# VER2.net
KiCad netlist of a schematic drawn in EAGLE
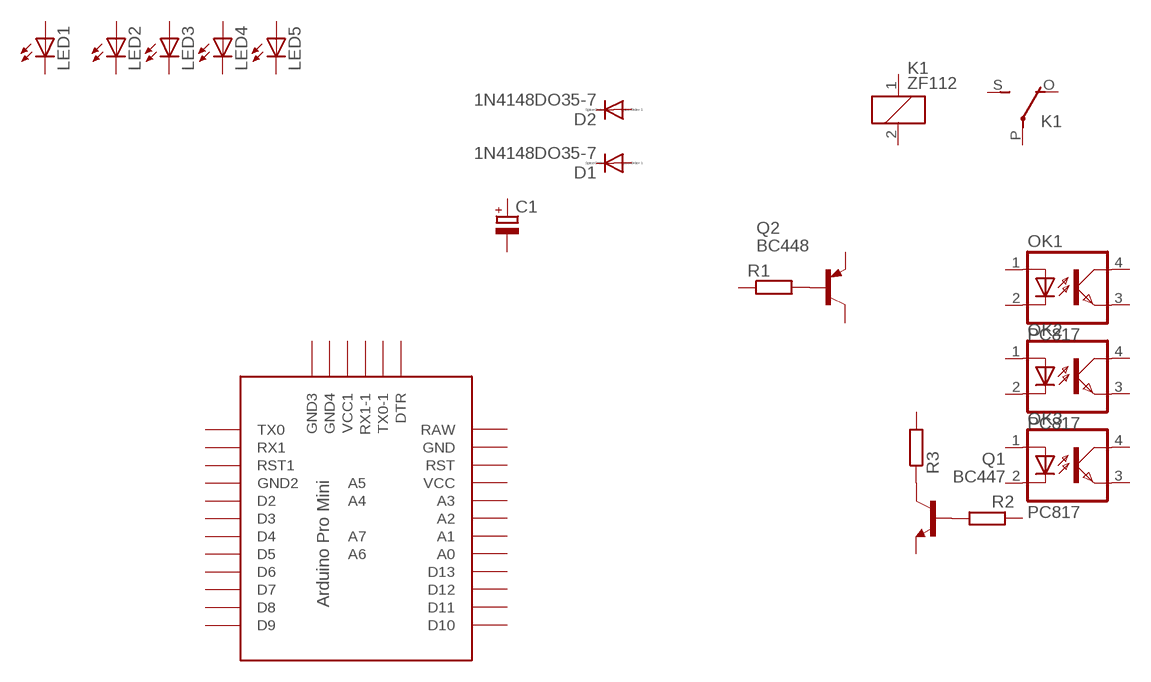
[diagram p0: schematic, sheet 1]

(export (version "E")
  (design (tool "Eeschema 10.0.6"))
  (components
    (comp (ref "C1")
      (value "CPOL-EUE5-6")
      (footprint "eagle-import:E5-6")
      (libsource (lib "eagle-import") (part "CPOL-EUE5-6"))
    )
    (comp (ref "D1")
      (value "1N4148DO35-7")
      (footprint "eagle-import:DO35-7")
      (libsource (lib "eagle-import") (part "1N4148DO35-7"))
    )
    (comp (ref "D2")
      (value "1N4148DO35-7")
      (footprint "eagle-import:DO35-7")
      (libsource (lib "eagle-import") (part "1N4148DO35-7"))
    )
    (comp (ref "K1")
      (value "ZF112")
      (footprint "eagle-import:ZF112")
      (libsource (lib "eagle-import") (part "ZF112"))
    )
    (comp (ref "LED1")
      (value "LED5MM")
      (footprint "eagle-import:LED5MM")
      (libsource (lib "eagle-import") (part "LED5MM"))
    )
    (comp (ref "LED2")
      (value "LED5MM")
      (footprint "eagle-import:LED5MM")
      (libsource (lib "eagle-import") (part "LED5MM"))
    )
    (comp (ref "LED3")
      (value "LED5MM")
      (footprint "eagle-import:LED5MM")
      (libsource (lib "eagle-import") (part "LED5MM"))
    )
    (comp (ref "LED4")
      (value "LED5MM")
      (footprint "eagle-import:LED5MM")
      (libsource (lib "eagle-import") (part "LED5MM"))
    )
    (comp (ref "LED5")
      (value "LED5MM")
      (footprint "eagle-import:LED5MM")
      (libsource (lib "eagle-import") (part "LED5MM"))
    )
    (comp (ref "OK1")
      (value "PC817")
      (footprint "eagle-import:DIL04")
      (fields (field (name "MPN") "PC817X4J000F"))
      (libsource (lib "eagle-import") (part "PC817"))
    )
    (comp (ref "OK2")
      (value "PC817")
      (footprint "eagle-import:DIL04")
      (fields (field (name "MPN") "PC817X4J000F"))
      (libsource (lib "eagle-import") (part "PC817"))
    )
    (comp (ref "OK3")
      (value "PC817")
      (footprint "eagle-import:DIL04")
      (fields (field (name "MPN") "PC817X4J000F"))
      (libsource (lib "eagle-import") (part "PC817"))
    )
    (comp (ref "Q1")
      (value "BC447")
      (footprint "eagle-import:TO92-EBC")
      (libsource (lib "eagle-import") (part "BC447"))
    )
    (comp (ref "Q2")
      (value "BC448")
      (footprint "eagle-import:TO92-EBC")
      (libsource (lib "eagle-import") (part "BC448"))
    )
    (comp (ref "R1")
      (value "R-EU_0207/7")
      (footprint "eagle-import:0207_7")
      (libsource (lib "eagle-import") (part "R-EU_0207/7"))
    )
    (comp (ref "R2")
      (value "R-EU_0207/7")
      (footprint "eagle-import:0207_7")
      (libsource (lib "eagle-import") (part "R-EU_0207/7"))
    )
    (comp (ref "R3")
      (value "R-EU_0207/7")
      (footprint "eagle-import:0207_7")
      (libsource (lib "eagle-import") (part "R-EU_0207/7"))
    )
    (comp (ref "U$1")
      (value "PRO-MINI-2")
      (footprint "eagle-import:PRO-MINI-2")
      (libsource (lib "eagle-import") (part "PRO-MINI-2"))
    )
  )
  (nets
    (net (code "1") (name "Net-(Q1-PadB)") (class "Default")
      (node (ref "Q1") (pin "B") (pinfunction "B_B") (pintype "passive"))
      (node (ref "R2") (pin "2") (pinfunction "2_2") (pintype "passive"))
    )
    (net (code "2") (name "Net-(Q1-PadC)") (class "Default")
      (node (ref "Q1") (pin "C") (pinfunction "C_C") (pintype "passive"))
      (node (ref "R3") (pin "1") (pinfunction "1_1") (pintype "passive"))
    )
    (net (code "3") (name "Net-(Q2-PadB)") (class "Default")
      (node (ref "Q2") (pin "B") (pinfunction "B_B") (pintype "passive"))
      (node (ref "R1") (pin "2") (pinfunction "2_2") (pintype "passive"))
    )
    (net (code "4") (name "unconnected-(C1-Pad+)") (class "Default")
      (node (ref "C1") (pin "+") (pinfunction "+_+") (pintype "passive"))
    )
    (net (code "5") (name "unconnected-(C1-Pad-)") (class "Default")
      (node (ref "C1") (pin "-") (pinfunction "-_-") (pintype "passive"))
    )
    (net (code "6") (name "unconnected-(D1-PadA)") (class "Default")
      (node (ref "D1") (pin "A") (pinfunction "A_A") (pintype "passive"))
    )
    (net (code "7") (name "unconnected-(D1-PadC)") (class "Default")
      (node (ref "D1") (pin "C") (pinfunction "C_C") (pintype "passive"))
    )
    (net (code "8") (name "unconnected-(D2-PadA)") (class "Default")
      (node (ref "D2") (pin "A") (pinfunction "A_A") (pintype "passive"))
    )
    (net (code "9") (name "unconnected-(D2-PadC)") (class "Default")
      (node (ref "D2") (pin "C") (pinfunction "C_C") (pintype "passive"))
    )
    (net (code "10") (name "unconnected-(K1-Pad1)") (class "Default")
      (node (ref "K1") (pin "1") (pinfunction "1_1") (pintype "passive"))
    )
    (net (code "11") (name "unconnected-(K1-Pad2)") (class "Default")
      (node (ref "K1") (pin "2") (pinfunction "2_2") (pintype "passive"))
    )
    (net (code "12") (name "unconnected-(K1-PadO)") (class "Default")
      (node (ref "K1") (pin "O") (pinfunction "O_O") (pintype "passive"))
    )
    (net (code "13") (name "unconnected-(K1-PadP)") (class "Default")
      (node (ref "K1") (pin "P") (pinfunction "P_P") (pintype "passive"))
    )
    (net (code "14") (name "unconnected-(K1-PadS)") (class "Default")
      (node (ref "K1") (pin "S") (pinfunction "S_S") (pintype "passive"))
    )
    (net (code "15") (name "unconnected-(LED1-C-PadK)") (class "Default")
      (node (ref "LED1") (pin "K") (pinfunction "C_K") (pintype "passive"))
    )
    (net (code "16") (name "unconnected-(LED1-PadA)") (class "Default")
      (node (ref "LED1") (pin "A") (pinfunction "A_A") (pintype "passive"))
    )
    (net (code "17") (name "unconnected-(LED2-C-PadK)") (class "Default")
      (node (ref "LED2") (pin "K") (pinfunction "C_K") (pintype "passive"))
    )
    (net (code "18") (name "unconnected-(LED2-PadA)") (class "Default")
      (node (ref "LED2") (pin "A") (pinfunction "A_A") (pintype "passive"))
    )
    (net (code "19") (name "unconnected-(LED3-C-PadK)") (class "Default")
      (node (ref "LED3") (pin "K") (pinfunction "C_K") (pintype "passive"))
    )
    (net (code "20") (name "unconnected-(LED3-PadA)") (class "Default")
      (node (ref "LED3") (pin "A") (pinfunction "A_A") (pintype "passive"))
    )
    (net (code "21") (name "unconnected-(LED4-C-PadK)") (class "Default")
      (node (ref "LED4") (pin "K") (pinfunction "C_K") (pintype "passive"))
    )
    (net (code "22") (name "unconnected-(LED4-PadA)") (class "Default")
      (node (ref "LED4") (pin "A") (pinfunction "A_A") (pintype "passive"))
    )
    (net (code "23") (name "unconnected-(LED5-C-PadK)") (class "Default")
      (node (ref "LED5") (pin "K") (pinfunction "C_K") (pintype "passive"))
    )
    (net (code "24") (name "unconnected-(LED5-PadA)") (class "Default")
      (node (ref "LED5") (pin "A") (pinfunction "A_A") (pintype "passive"))
    )
    (net (code "25") (name "unconnected-(OK1-A-Pad1)") (class "Default")
      (node (ref "OK1") (pin "1") (pinfunction "A_1") (pintype "passive"))
    )
    (net (code "26") (name "unconnected-(OK1-C-Pad2)") (class "Default")
      (node (ref "OK1") (pin "2") (pinfunction "C_2") (pintype "passive"))
    )
    (net (code "27") (name "unconnected-(OK1-COL-Pad4)") (class "Default")
      (node (ref "OK1") (pin "4") (pinfunction "COL_4") (pintype "passive"))
    )
    (net (code "28") (name "unconnected-(OK1-EMIT-Pad3)") (class "Default")
      (node (ref "OK1") (pin "3") (pinfunction "EMIT_3") (pintype "passive"))
    )
    (net (code "29") (name "unconnected-(OK2-A-Pad1)") (class "Default")
      (node (ref "OK2") (pin "1") (pinfunction "A_1") (pintype "passive"))
    )
    (net (code "30") (name "unconnected-(OK2-C-Pad2)") (class "Default")
      (node (ref "OK2") (pin "2") (pinfunction "C_2") (pintype "passive"))
    )
    (net (code "31") (name "unconnected-(OK2-COL-Pad4)") (class "Default")
      (node (ref "OK2") (pin "4") (pinfunction "COL_4") (pintype "passive"))
    )
    (net (code "32") (name "unconnected-(OK2-EMIT-Pad3)") (class "Default")
      (node (ref "OK2") (pin "3") (pinfunction "EMIT_3") (pintype "passive"))
    )
    (net (code "33") (name "unconnected-(OK3-A-Pad1)") (class "Default")
      (node (ref "OK3") (pin "1") (pinfunction "A_1") (pintype "passive"))
    )
    (net (code "34") (name "unconnected-(OK3-C-Pad2)") (class "Default")
      (node (ref "OK3") (pin "2") (pinfunction "C_2") (pintype "passive"))
    )
    (net (code "35") (name "unconnected-(OK3-COL-Pad4)") (class "Default")
      (node (ref "OK3") (pin "4") (pinfunction "COL_4") (pintype "passive"))
    )
    (net (code "36") (name "unconnected-(OK3-EMIT-Pad3)") (class "Default")
      (node (ref "OK3") (pin "3") (pinfunction "EMIT_3") (pintype "passive"))
    )
    (net (code "37") (name "unconnected-(Q1-PadE)") (class "Default")
      (node (ref "Q1") (pin "E") (pinfunction "E_E") (pintype "passive"))
    )
    (net (code "38") (name "unconnected-(Q2-PadC)") (class "Default")
      (node (ref "Q2") (pin "C") (pinfunction "C_C") (pintype "passive"))
    )
    (net (code "39") (name "unconnected-(Q2-PadE)") (class "Default")
      (node (ref "Q2") (pin "E") (pinfunction "E_E") (pintype "passive"))
    )
    (net (code "40") (name "unconnected-(R1-Pad1)") (class "Default")
      (node (ref "R1") (pin "1") (pinfunction "1_1") (pintype "passive"))
    )
    (net (code "41") (name "unconnected-(R2-Pad1)") (class "Default")
      (node (ref "R2") (pin "1") (pinfunction "1_1") (pintype "passive"))
    )
    (net (code "42") (name "unconnected-(R3-Pad2)") (class "Default")
      (node (ref "R3") (pin "2") (pinfunction "2_2") (pintype "passive"))
    )
    (net (code "43") (name "unconnected-(U$1-GND2-PadGND1)") (class "Default")
      (node (ref "U$1") (pin "GND1") (pinfunction "GND2_GND1") (pintype "bidirectional"))
    )
    (net (code "44") (name "unconnected-(U$1-GND3-PadGND2)") (class "Default")
      (node (ref "U$1") (pin "GND2") (pinfunction "GND3_GND2") (pintype "bidirectional"))
    )
    (net (code "45") (name "unconnected-(U$1-GND4-PadGND3)") (class "Default")
      (node (ref "U$1") (pin "GND3") (pinfunction "GND4_GND3") (pintype "bidirectional"))
    )
    (net (code "46") (name "unconnected-(U$1-PadA0)") (class "Default")
      (node (ref "U$1") (pin "A0") (pinfunction "A0_A0") (pintype "bidirectional"))
    )
    (net (code "47") (name "unconnected-(U$1-PadA1)") (class "Default")
      (node (ref "U$1") (pin "A1") (pinfunction "A1_A1") (pintype "bidirectional"))
    )
    (net (code "48") (name "unconnected-(U$1-PadA2)") (class "Default")
      (node (ref "U$1") (pin "A2") (pinfunction "A2_A2") (pintype "bidirectional"))
    )
    (net (code "49") (name "unconnected-(U$1-PadA3)") (class "Default")
      (node (ref "U$1") (pin "A3") (pinfunction "A3_A3") (pintype "bidirectional"))
    )
    (net (code "50") (name "unconnected-(U$1-PadA4)") (class "Default")
      (node (ref "U$1") (pin "A4") (pinfunction "A4_A4") (pintype "bidirectional"))
    )
    (net (code "51") (name "unconnected-(U$1-PadA5)") (class "Default")
      (node (ref "U$1") (pin "A5") (pinfunction "A5_A5") (pintype "bidirectional"))
    )
    (net (code "52") (name "unconnected-(U$1-PadA6)") (class "Default")
      (node (ref "U$1") (pin "A6") (pinfunction "A6_A6") (pintype "bidirectional"))
    )
    (net (code "53") (name "unconnected-(U$1-PadA7)") (class "Default")
      (node (ref "U$1") (pin "A7") (pinfunction "A7_A7") (pintype "bidirectional"))
    )
    (net (code "54") (name "unconnected-(U$1-PadD2)") (class "Default")
      (node (ref "U$1") (pin "D2") (pinfunction "D2_D2") (pintype "bidirectional"))
    )
    (net (code "55") (name "unconnected-(U$1-PadD3)") (class "Default")
      (node (ref "U$1") (pin "D3") (pinfunction "D3_D3") (pintype "bidirectional"))
    )
    (net (code "56") (name "unconnected-(U$1-PadD4)") (class "Default")
      (node (ref "U$1") (pin "D4") (pinfunction "D4_D4") (pintype "bidirectional"))
    )
    (net (code "57") (name "unconnected-(U$1-PadD5)") (class "Default")
      (node (ref "U$1") (pin "D5") (pinfunction "D5_D5") (pintype "bidirectional"))
    )
    (net (code "58") (name "unconnected-(U$1-PadD6)") (class "Default")
      (node (ref "U$1") (pin "D6") (pinfunction "D6_D6") (pintype "bidirectional"))
    )
    (net (code "59") (name "unconnected-(U$1-PadD7)") (class "Default")
      (node (ref "U$1") (pin "D7") (pinfunction "D7_D7") (pintype "bidirectional"))
    )
    (net (code "60") (name "unconnected-(U$1-PadD8)") (class "Default")
      (node (ref "U$1") (pin "D8") (pinfunction "D8_D8") (pintype "bidirectional"))
    )
    (net (code "61") (name "unconnected-(U$1-PadD9)") (class "Default")
      (node (ref "U$1") (pin "D9") (pinfunction "D9_D9") (pintype "bidirectional"))
    )
    (net (code "62") (name "unconnected-(U$1-PadD10)") (class "Default")
      (node (ref "U$1") (pin "D10") (pinfunction "D10_D10") (pintype "bidirectional"))
    )
    (net (code "63") (name "unconnected-(U$1-PadD11)") (class "Default")
      (node (ref "U$1") (pin "D11") (pinfunction "D11_D11") (pintype "bidirectional"))
    )
    (net (code "64") (name "unconnected-(U$1-PadD12)") (class "Default")
      (node (ref "U$1") (pin "D12") (pinfunction "D12_D12") (pintype "bidirectional"))
    )
    (net (code "65") (name "unconnected-(U$1-PadD13)") (class "Default")
      (node (ref "U$1") (pin "D13") (pinfunction "D13_D13") (pintype "bidirectional"))
    )
    (net (code "66") (name "unconnected-(U$1-PadDTR)") (class "Default")
      (node (ref "U$1") (pin "DTR") (pinfunction "DTR_DTR") (pintype "bidirectional"))
    )
    (net (code "67") (name "unconnected-(U$1-PadGND)") (class "Default")
      (node (ref "U$1") (pin "GND") (pinfunction "GND_GND") (pintype "bidirectional"))
    )
    (net (code "68") (name "unconnected-(U$1-PadRAW)") (class "Default")
      (node (ref "U$1") (pin "RAW") (pinfunction "RAW_RAW") (pintype "bidirectional"))
    )
    (net (code "69") (name "unconnected-(U$1-PadRST)") (class "Default")
      (node (ref "U$1") (pin "RST") (pinfunction "RST_RST") (pintype "bidirectional"))
    )
    (net (code "70") (name "unconnected-(U$1-PadRST1)") (class "Default")
      (node (ref "U$1") (pin "RST1") (pinfunction "RST1_RST1") (pintype "bidirectional"))
    )
    (net (code "71") (name "unconnected-(U$1-PadRX1)") (class "Default")
      (node (ref "U$1") (pin "RX1") (pinfunction "RX1_RX1") (pintype "bidirectional"))
    )
    (net (code "72") (name "unconnected-(U$1-PadRX1-1)") (class "Default")
      (node (ref "U$1") (pin "RX1-1") (pinfunction "RX1-1_RX1-1") (pintype "bidirectional"))
    )
    (net (code "73") (name "unconnected-(U$1-PadTX0)") (class "Default")
      (node (ref "U$1") (pin "TX0") (pinfunction "TX0_TX0") (pintype "bidirectional"))
    )
    (net (code "74") (name "unconnected-(U$1-PadTX0-1)") (class "Default")
      (node (ref "U$1") (pin "TX0-1") (pinfunction "TX0-1_TX0-1") (pintype "bidirectional"))
    )
    (net (code "75") (name "unconnected-(U$1-PadVCC)") (class "Default")
      (node (ref "U$1") (pin "VCC") (pinfunction "VCC_VCC") (pintype "bidirectional"))
    )
    (net (code "76") (name "unconnected-(U$1-PadVCC1)") (class "Default")
      (node (ref "U$1") (pin "VCC1") (pinfunction "VCC1_VCC1") (pintype "bidirectional"))
    )
  )
)
